# Connector_Schematic.net
KiCad netlist of a schematic drawn in Altium Designer
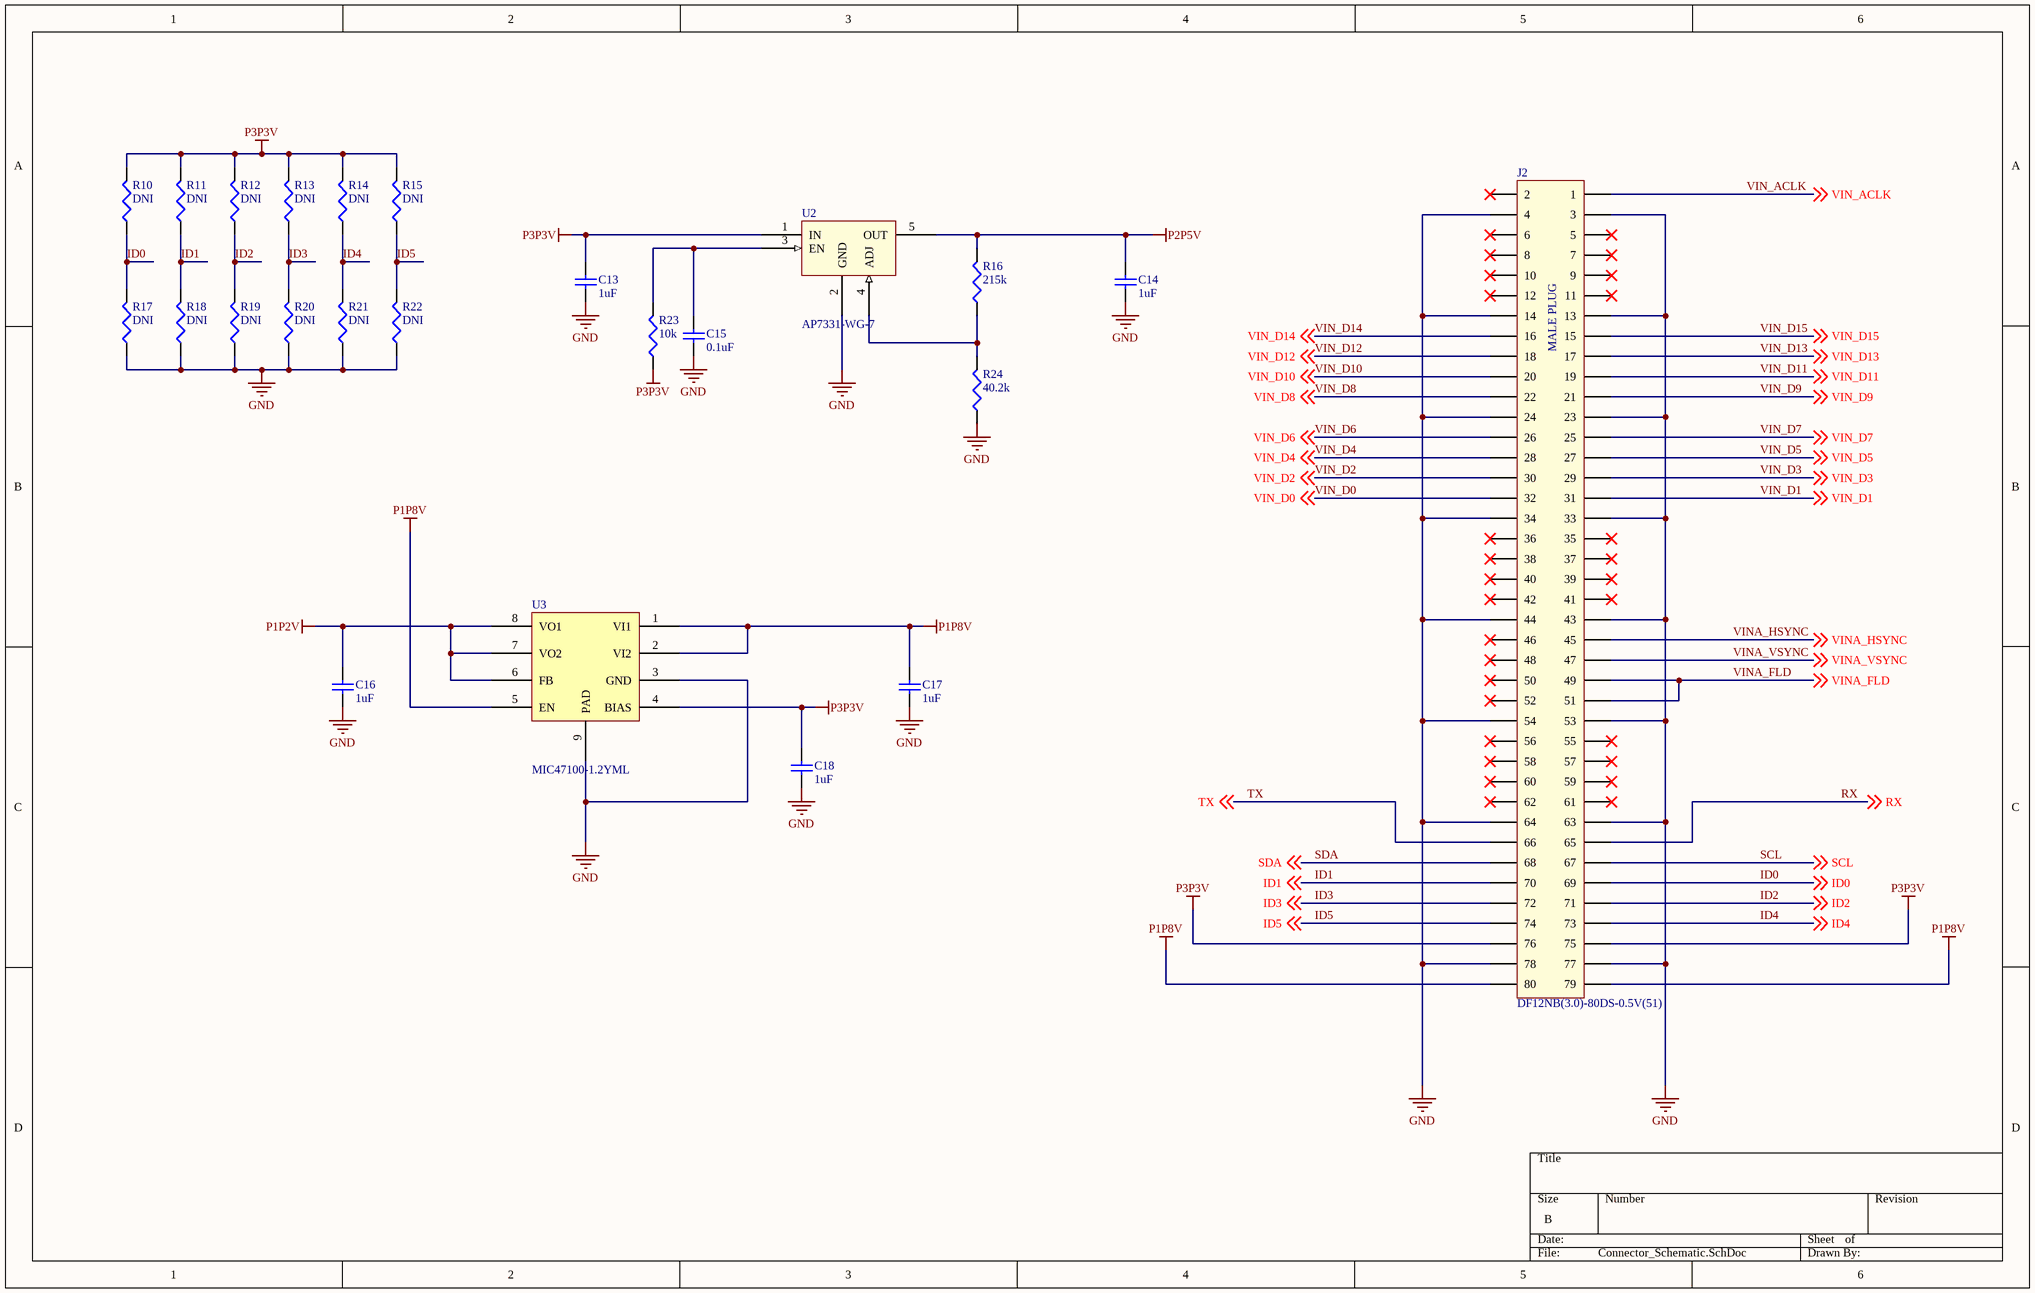
[diagram p0: Connector_Schematic.SchDoc]

(export (version "E")
  (design (tool "Eeschema 10.0.6"))
  (components
    (comp (ref "C13")
      (value "1uF")
      (footprint "INDC1005X45")
      (description "CAP CER 1UF 25V X5R 0402")
      (fields (field (name "MFGPARTNO") "EMK105BJ105KV-F") (field (name "MFG") "Taiyo Yuden"))
      (libsource (lib "SLA3000-FPGA[4086]") (part "CMP-00695-A.2"))
    )
    (comp (ref "C14")
      (value "1uF")
      (footprint "INDC1005X45")
      (description "CAP CER 1UF 25V X5R 0402")
      (fields (field (name "MFGPARTNO") "EMK105BJ105KV-F") (field (name "MFG") "Taiyo Yuden"))
      (libsource (lib "SLA3000-FPGA[4086]") (part "CMP-00695-A.2"))
    )
    (comp (ref "C15")
      (value "0.1uF")
      (footprint "INDC1005X45")
      (description "CAP CER 0.1UF 25V X7R 0402")
      (fields (field (name "SLA PART NO") "SL00150") (field (name "MFG") "TDK"))
      (libsource (lib "SLA3000-FPGA[4086]") (part "CMP-00496-A.6"))
    )
    (comp (ref "C16")
      (value "1uF")
      (footprint "INDC1005X45")
      (description "CAP CER 1UF 25V X5R 0402")
      (fields (field (name "MFGPARTNO") "EMK105BJ105KV-F") (field (name "MFG") "Taiyo Yuden"))
      (libsource (lib "SLA3000-FPGA[4086]") (part "CMP-00695-A.2"))
    )
    (comp (ref "C17")
      (value "1uF")
      (footprint "INDC1005X45")
      (description "CAP CER 1UF 25V X5R 0402")
      (fields (field (name "MFGPARTNO") "EMK105BJ105KV-F") (field (name "MFG") "Taiyo Yuden"))
      (libsource (lib "SLA3000-FPGA[4086]") (part "CMP-00695-A.2"))
    )
    (comp (ref "C18")
      (value "1uF")
      (footprint "INDC1005X45")
      (description "CAP CER 1UF 25V X5R 0402")
      (fields (field (name "MFGPARTNO") "EMK105BJ105KV-F") (field (name "MFG") "Taiyo Yuden"))
      (libsource (lib "SLA3000-FPGA[4086]") (part "CMP-00695-A.2"))
    )
    (comp (ref "J2")
      (value "DF12NB(3.0)-80DS-0.5V(51)")
      (footprint "DF12NB(3.0)-80DS-0.5V(51)")
      (description "DF12NB(3.0)-80DS-0.5V(51) HIROSE CONN HEADER 80POS 3MM SMD 0.5MM")
      (fields (field (name "MFG") "Hirose"))
      (libsource (lib "SLA3000-FPGA[4086]") (part "CMP-00854-A.1"))
    )
    (comp (ref "R10")
      (value "DNI")
      (footprint "RES_ERJU02F1241X")
      (description "Do Not Populate 0402 Res")
      (libsource (lib "SLA3000-FPGA[4086]") (part "CMP-00432-A.10"))
    )
    (comp (ref "R11")
      (value "DNI")
      (footprint "RES_ERJU02F1241X")
      (description "Do Not Populate 0402 Res")
      (libsource (lib "SLA3000-FPGA[4086]") (part "CMP-00432-A.10"))
    )
    (comp (ref "R12")
      (value "DNI")
      (footprint "RES_ERJU02F1241X")
      (description "Do Not Populate 0402 Res")
      (libsource (lib "SLA3000-FPGA[4086]") (part "CMP-00432-A.10"))
    )
    (comp (ref "R13")
      (value "DNI")
      (footprint "RES_ERJU02F1241X")
      (description "Do Not Populate 0402 Res")
      (libsource (lib "SLA3000-FPGA[4086]") (part "CMP-00432-A.10"))
    )
    (comp (ref "R14")
      (value "DNI")
      (footprint "RES_ERJU02F1241X")
      (description "Do Not Populate 0402 Res")
      (libsource (lib "SLA3000-FPGA[4086]") (part "CMP-00432-A.10"))
    )
    (comp (ref "R15")
      (value "DNI")
      (footprint "RES_ERJU02F1241X")
      (description "Do Not Populate 0402 Res")
      (libsource (lib "SLA3000-FPGA[4086]") (part "CMP-00432-A.10"))
    )
    (comp (ref "R16")
      (value "215k")
      (footprint "RES_ERJU02F1241X")
      (description "RES SMD 215K OHM 1% 1/16W 0402")
      (fields (field (name "MFGPARTNO") "RC0402FR-07215KL") (field (name "MFG") "Yageo"))
      (libsource (lib "SLA3000-FPGA[4086]") (part "CMP-00638-A.1"))
    )
    (comp (ref "R17")
      (value "DNI")
      (footprint "RES_ERJU02F1241X")
      (description "Do Not Populate 0402 Res")
      (libsource (lib "SLA3000-FPGA[4086]") (part "CMP-00432-A.10"))
    )
    (comp (ref "R18")
      (value "DNI")
      (footprint "RES_ERJU02F1241X")
      (description "Do Not Populate 0402 Res")
      (libsource (lib "SLA3000-FPGA[4086]") (part "CMP-00432-A.10"))
    )
    (comp (ref "R19")
      (value "DNI")
      (footprint "RES_ERJU02F1241X")
      (description "Do Not Populate 0402 Res")
      (libsource (lib "SLA3000-FPGA[4086]") (part "CMP-00432-A.10"))
    )
    (comp (ref "R20")
      (value "DNI")
      (footprint "RES_ERJU02F1241X")
      (description "Do Not Populate 0402 Res")
      (libsource (lib "SLA3000-FPGA[4086]") (part "CMP-00432-A.10"))
    )
    (comp (ref "R21")
      (value "DNI")
      (footprint "RES_ERJU02F1241X")
      (description "Do Not Populate 0402 Res")
      (libsource (lib "SLA3000-FPGA[4086]") (part "CMP-00432-A.10"))
    )
    (comp (ref "R22")
      (value "DNI")
      (footprint "RES_ERJU02F1241X")
      (description "Do Not Populate 0402 Res")
      (libsource (lib "SLA3000-FPGA[4086]") (part "CMP-00432-A.10"))
    )
    (comp (ref "R23")
      (value "10k")
      (footprint "RES_ERJU02F1241X")
      (description "RES SMD 10K OHM 1% 1/10W 0402")
      (fields (field (name "SLA PART NO") "SL00225") (field (name "MFG") "Panasonic"))
      (libsource (lib "SLA3000-FPGA[4086]") (part "CMP-00396-A.9"))
    )
    (comp (ref "R24")
      (value "40.2k")
      (footprint "RES_ERJU02F1241X")
      (description "RES 40.2K OHM 1/10W 1% 0402 SMD")
      (fields (field (name "SLA PART NO") "SL00235") (field (name "MFGPARTNO") "ERJ-2RKF4022X"))
      (libsource (lib "SLA3000-FPGA[4086]") (part "CMP-00410-A.9"))
    )
    (comp (ref "U2")
      (value "AP7331-WG-7")
      (footprint "SOT95P285X140-5N")
      (description "Adj 0.8-5V Out, 2-6V In, 300mA, AP7331-WG-7 LDO SOT23-5")
      (fields (field (name "SLA PART NO") "SL00740") (field (name "MFG") "Diodes Inc."))
      (libsource (lib "SLA3000-FPGA[4086]") (part "CMP-00547-A.3"))
    )
    (comp (ref "U3")
      (value "MIC47100-1.2YML")
      (footprint "SON50P250X250X75-9N")
      (description "1.2V, 1A, MIC47100-1.2TML IC REG LDO 8MLF")
      (fields (field (name "MFG") "Micrel") (field (name "SLA PART NO") "SL00247"))
      (libsource (lib "SLA3000-FPGA[4086]") (part "CMP-00239-A.3"))
    )
  )
  (nets
    (net (code "1") (name "GND") (class "Default")
      (node (ref "C13") (pin "1") (pinfunction "1_1") (pintype "passive"))
      (node (ref "C14") (pin "1") (pinfunction "1_1") (pintype "passive"))
      (node (ref "C15") (pin "1") (pinfunction "1_1") (pintype "passive"))
      (node (ref "C16") (pin "1") (pinfunction "1_1") (pintype "passive"))
      (node (ref "C17") (pin "1") (pinfunction "1_1") (pintype "passive"))
      (node (ref "C18") (pin "1") (pinfunction "1_1") (pintype "passive"))
      (node (ref "J2") (pin "13") (pinfunction "13_13") (pintype "passive"))
      (node (ref "J2") (pin "14") (pinfunction "14_14") (pintype "passive"))
      (node (ref "J2") (pin "23") (pinfunction "23_23") (pintype "passive"))
      (node (ref "J2") (pin "24") (pinfunction "24_24") (pintype "passive"))
      (node (ref "J2") (pin "3") (pinfunction "3_3") (pintype "passive"))
      (node (ref "J2") (pin "33") (pinfunction "33_33") (pintype "passive"))
      (node (ref "J2") (pin "34") (pinfunction "34_34") (pintype "passive"))
      (node (ref "J2") (pin "4") (pinfunction "4_4") (pintype "passive"))
      (node (ref "J2") (pin "43") (pinfunction "43_43") (pintype "passive"))
      (node (ref "J2") (pin "44") (pinfunction "44_44") (pintype "passive"))
      (node (ref "J2") (pin "53") (pinfunction "53_53") (pintype "passive"))
      (node (ref "J2") (pin "54") (pinfunction "54_54") (pintype "passive"))
      (node (ref "J2") (pin "63") (pinfunction "63_63") (pintype "passive"))
      (node (ref "J2") (pin "64") (pinfunction "64_64") (pintype "passive"))
      (node (ref "J2") (pin "77") (pinfunction "77_77") (pintype "passive"))
      (node (ref "J2") (pin "78") (pinfunction "78_78") (pintype "passive"))
      (node (ref "R17") (pin "1") (pinfunction "1_1") (pintype "passive"))
      (node (ref "R18") (pin "1") (pinfunction "1_1") (pintype "passive"))
      (node (ref "R19") (pin "1") (pinfunction "1_1") (pintype "passive"))
      (node (ref "R20") (pin "1") (pinfunction "1_1") (pintype "passive"))
      (node (ref "R21") (pin "1") (pinfunction "1_1") (pintype "passive"))
      (node (ref "R22") (pin "1") (pinfunction "1_1") (pintype "passive"))
      (node (ref "R24") (pin "1") (pinfunction "1_1") (pintype "passive"))
      (node (ref "U2") (pin "2") (pinfunction "GND_2") (pintype "power_in"))
      (node (ref "U3") (pin "3") (pinfunction "GND_3") (pintype "passive"))
      (node (ref "U3") (pin "9") (pinfunction "PAD_9") (pintype "passive"))
    )
    (net (code "2") (name "ID0") (class "Default")
      (node (ref "J2") (pin "69") (pinfunction "69_69") (pintype "passive"))
      (node (ref "R10") (pin "1") (pinfunction "1_1") (pintype "passive"))
      (node (ref "R17") (pin "2") (pinfunction "2_2") (pintype "passive"))
    )
    (net (code "3") (name "ID1") (class "Default")
      (node (ref "J2") (pin "70") (pinfunction "70_70") (pintype "passive"))
      (node (ref "R11") (pin "1") (pinfunction "1_1") (pintype "passive"))
      (node (ref "R18") (pin "2") (pinfunction "2_2") (pintype "passive"))
    )
    (net (code "4") (name "ID2") (class "Default")
      (node (ref "J2") (pin "71") (pinfunction "71_71") (pintype "passive"))
      (node (ref "R12") (pin "1") (pinfunction "1_1") (pintype "passive"))
      (node (ref "R19") (pin "2") (pinfunction "2_2") (pintype "passive"))
    )
    (net (code "5") (name "ID3") (class "Default")
      (node (ref "J2") (pin "72") (pinfunction "72_72") (pintype "passive"))
      (node (ref "R13") (pin "1") (pinfunction "1_1") (pintype "passive"))
      (node (ref "R20") (pin "2") (pinfunction "2_2") (pintype "passive"))
    )
    (net (code "6") (name "ID4") (class "Default")
      (node (ref "J2") (pin "73") (pinfunction "73_73") (pintype "passive"))
      (node (ref "R14") (pin "1") (pinfunction "1_1") (pintype "passive"))
      (node (ref "R21") (pin "2") (pinfunction "2_2") (pintype "passive"))
    )
    (net (code "7") (name "ID5") (class "Default")
      (node (ref "J2") (pin "74") (pinfunction "74_74") (pintype "passive"))
      (node (ref "R15") (pin "1") (pinfunction "1_1") (pintype "passive"))
      (node (ref "R22") (pin "2") (pinfunction "2_2") (pintype "passive"))
    )
    (net (code "8") (name "Net-(U2-ADJ)") (class "Default")
      (node (ref "R16") (pin "1") (pinfunction "1_1") (pintype "passive"))
      (node (ref "R24") (pin "2") (pinfunction "2_2") (pintype "passive"))
      (node (ref "U2") (pin "4") (pinfunction "ADJ_4") (pintype "input"))
    )
    (net (code "9") (name "Net-(U2-EN)") (class "Default")
      (node (ref "C15") (pin "2") (pinfunction "2_2") (pintype "passive"))
      (node (ref "R23") (pin "2") (pinfunction "2_2") (pintype "passive"))
      (node (ref "U2") (pin "3") (pinfunction "EN_3") (pintype "input"))
    )
    (net (code "10") (name "P1P2V") (class "Default")
      (node (ref "C16") (pin "2") (pinfunction "2_2") (pintype "passive"))
      (node (ref "U3") (pin "6") (pinfunction "FB_6") (pintype "passive"))
      (node (ref "U3") (pin "7") (pinfunction "VO2_7") (pintype "passive"))
      (node (ref "U3") (pin "8") (pinfunction "VO1_8") (pintype "passive"))
    )
    (net (code "11") (name "P1P8V") (class "Default")
      (node (ref "C17") (pin "2") (pinfunction "2_2") (pintype "passive"))
      (node (ref "J2") (pin "79") (pinfunction "79_79") (pintype "passive"))
      (node (ref "J2") (pin "80") (pinfunction "80_80") (pintype "passive"))
      (node (ref "U3") (pin "1") (pinfunction "VI1_1") (pintype "passive"))
      (node (ref "U3") (pin "2") (pinfunction "VI2_2") (pintype "passive"))
      (node (ref "U3") (pin "5") (pinfunction "EN_5") (pintype "passive"))
    )
    (net (code "12") (name "P2P5V") (class "Default")
      (node (ref "C14") (pin "2") (pinfunction "2_2") (pintype "passive"))
      (node (ref "R16") (pin "2") (pinfunction "2_2") (pintype "passive"))
      (node (ref "U2") (pin "5") (pinfunction "OUT_5") (pintype "power_in"))
    )
    (net (code "13") (name "P3P3V") (class "Default")
      (node (ref "C13") (pin "2") (pinfunction "2_2") (pintype "passive"))
      (node (ref "C18") (pin "2") (pinfunction "2_2") (pintype "passive"))
      (node (ref "J2") (pin "75") (pinfunction "75_75") (pintype "passive"))
      (node (ref "J2") (pin "76") (pinfunction "76_76") (pintype "passive"))
      (node (ref "R10") (pin "2") (pinfunction "2_2") (pintype "passive"))
      (node (ref "R11") (pin "2") (pinfunction "2_2") (pintype "passive"))
      (node (ref "R12") (pin "2") (pinfunction "2_2") (pintype "passive"))
      (node (ref "R13") (pin "2") (pinfunction "2_2") (pintype "passive"))
      (node (ref "R14") (pin "2") (pinfunction "2_2") (pintype "passive"))
      (node (ref "R15") (pin "2") (pinfunction "2_2") (pintype "passive"))
      (node (ref "R23") (pin "1") (pinfunction "1_1") (pintype "passive"))
      (node (ref "U2") (pin "1") (pinfunction "IN_1") (pintype "power_in"))
      (node (ref "U3") (pin "4") (pinfunction "BIAS_4") (pintype "passive"))
    )
    (net (code "14") (name "RX") (class "Default")
      (node (ref "J2") (pin "65") (pinfunction "65_65") (pintype "passive"))
    )
    (net (code "15") (name "SCL") (class "Default")
      (node (ref "J2") (pin "67") (pinfunction "67_67") (pintype "passive"))
    )
    (net (code "16") (name "SDA") (class "Default")
      (node (ref "J2") (pin "68") (pinfunction "68_68") (pintype "passive"))
    )
    (net (code "17") (name "TX") (class "Default")
      (node (ref "J2") (pin "66") (pinfunction "66_66") (pintype "passive"))
    )
    (net (code "18") (name "VINA_FLD") (class "Default")
      (node (ref "J2") (pin "49") (pinfunction "49_49") (pintype "passive"))
      (node (ref "J2") (pin "51") (pinfunction "51_51") (pintype "passive"))
    )
    (net (code "19") (name "VINA_HSYNC") (class "Default")
      (node (ref "J2") (pin "45") (pinfunction "45_45") (pintype "passive"))
    )
    (net (code "20") (name "VINA_VSYNC") (class "Default")
      (node (ref "J2") (pin "47") (pinfunction "47_47") (pintype "passive"))
    )
    (net (code "21") (name "VIN_ACLK") (class "Default")
      (node (ref "J2") (pin "1") (pinfunction "1_1") (pintype "passive"))
    )
    (net (code "22") (name "VIN_D0") (class "Default")
      (node (ref "J2") (pin "32") (pinfunction "32_32") (pintype "passive"))
    )
    (net (code "23") (name "VIN_D1") (class "Default")
      (node (ref "J2") (pin "31") (pinfunction "31_31") (pintype "passive"))
    )
    (net (code "24") (name "VIN_D2") (class "Default")
      (node (ref "J2") (pin "30") (pinfunction "30_30") (pintype "passive"))
    )
    (net (code "25") (name "VIN_D3") (class "Default")
      (node (ref "J2") (pin "29") (pinfunction "29_29") (pintype "passive"))
    )
    (net (code "26") (name "VIN_D4") (class "Default")
      (node (ref "J2") (pin "28") (pinfunction "28_28") (pintype "passive"))
    )
    (net (code "27") (name "VIN_D5") (class "Default")
      (node (ref "J2") (pin "27") (pinfunction "27_27") (pintype "passive"))
    )
    (net (code "28") (name "VIN_D6") (class "Default")
      (node (ref "J2") (pin "26") (pinfunction "26_26") (pintype "passive"))
    )
    (net (code "29") (name "VIN_D7") (class "Default")
      (node (ref "J2") (pin "25") (pinfunction "25_25") (pintype "passive"))
    )
    (net (code "30") (name "VIN_D8") (class "Default")
      (node (ref "J2") (pin "22") (pinfunction "22_22") (pintype "passive"))
    )
    (net (code "31") (name "VIN_D9") (class "Default")
      (node (ref "J2") (pin "21") (pinfunction "21_21") (pintype "passive"))
    )
    (net (code "32") (name "VIN_D10") (class "Default")
      (node (ref "J2") (pin "20") (pinfunction "20_20") (pintype "passive"))
    )
    (net (code "33") (name "VIN_D11") (class "Default")
      (node (ref "J2") (pin "19") (pinfunction "19_19") (pintype "passive"))
    )
    (net (code "34") (name "VIN_D12") (class "Default")
      (node (ref "J2") (pin "18") (pinfunction "18_18") (pintype "passive"))
    )
    (net (code "35") (name "VIN_D13") (class "Default")
      (node (ref "J2") (pin "17") (pinfunction "17_17") (pintype "passive"))
    )
    (net (code "36") (name "VIN_D14") (class "Default")
      (node (ref "J2") (pin "16") (pinfunction "16_16") (pintype "passive"))
    )
    (net (code "37") (name "VIN_D15") (class "Default")
      (node (ref "J2") (pin "15") (pinfunction "15_15") (pintype "passive"))
    )
    (net (code "38") (name "unconnected-(J2-Pad2)") (class "Default")
      (node (ref "J2") (pin "2") (pinfunction "2_2") (pintype "passive+no_connect"))
    )
    (net (code "39") (name "unconnected-(J2-Pad5)") (class "Default")
      (node (ref "J2") (pin "5") (pinfunction "5_5") (pintype "passive+no_connect"))
    )
    (net (code "40") (name "unconnected-(J2-Pad6)") (class "Default")
      (node (ref "J2") (pin "6") (pinfunction "6_6") (pintype "passive+no_connect"))
    )
    (net (code "41") (name "unconnected-(J2-Pad7)") (class "Default")
      (node (ref "J2") (pin "7") (pinfunction "7_7") (pintype "passive+no_connect"))
    )
    (net (code "42") (name "unconnected-(J2-Pad8)") (class "Default")
      (node (ref "J2") (pin "8") (pinfunction "8_8") (pintype "passive+no_connect"))
    )
    (net (code "43") (name "unconnected-(J2-Pad9)") (class "Default")
      (node (ref "J2") (pin "9") (pinfunction "9_9") (pintype "passive+no_connect"))
    )
    (net (code "44") (name "unconnected-(J2-Pad10)") (class "Default")
      (node (ref "J2") (pin "10") (pinfunction "10_10") (pintype "passive+no_connect"))
    )
    (net (code "45") (name "unconnected-(J2-Pad11)") (class "Default")
      (node (ref "J2") (pin "11") (pinfunction "11_11") (pintype "passive+no_connect"))
    )
    (net (code "46") (name "unconnected-(J2-Pad12)") (class "Default")
      (node (ref "J2") (pin "12") (pinfunction "12_12") (pintype "passive+no_connect"))
    )
    (net (code "47") (name "unconnected-(J2-Pad35)") (class "Default")
      (node (ref "J2") (pin "35") (pinfunction "35_35") (pintype "passive+no_connect"))
    )
    (net (code "48") (name "unconnected-(J2-Pad36)") (class "Default")
      (node (ref "J2") (pin "36") (pinfunction "36_36") (pintype "passive+no_connect"))
    )
    (net (code "49") (name "unconnected-(J2-Pad37)") (class "Default")
      (node (ref "J2") (pin "37") (pinfunction "37_37") (pintype "passive+no_connect"))
    )
    (net (code "50") (name "unconnected-(J2-Pad38)") (class "Default")
      (node (ref "J2") (pin "38") (pinfunction "38_38") (pintype "passive+no_connect"))
    )
    (net (code "51") (name "unconnected-(J2-Pad39)") (class "Default")
      (node (ref "J2") (pin "39") (pinfunction "39_39") (pintype "passive+no_connect"))
    )
    (net (code "52") (name "unconnected-(J2-Pad40)") (class "Default")
      (node (ref "J2") (pin "40") (pinfunction "40_40") (pintype "passive+no_connect"))
    )
    (net (code "53") (name "unconnected-(J2-Pad41)") (class "Default")
      (node (ref "J2") (pin "41") (pinfunction "41_41") (pintype "passive+no_connect"))
    )
    (net (code "54") (name "unconnected-(J2-Pad42)") (class "Default")
      (node (ref "J2") (pin "42") (pinfunction "42_42") (pintype "passive+no_connect"))
    )
    (net (code "55") (name "unconnected-(J2-Pad46)") (class "Default")
      (node (ref "J2") (pin "46") (pinfunction "46_46") (pintype "passive+no_connect"))
    )
    (net (code "56") (name "unconnected-(J2-Pad48)") (class "Default")
      (node (ref "J2") (pin "48") (pinfunction "48_48") (pintype "passive+no_connect"))
    )
    (net (code "57") (name "unconnected-(J2-Pad50)") (class "Default")
      (node (ref "J2") (pin "50") (pinfunction "50_50") (pintype "passive+no_connect"))
    )
    (net (code "58") (name "unconnected-(J2-Pad52)") (class "Default")
      (node (ref "J2") (pin "52") (pinfunction "52_52") (pintype "passive+no_connect"))
    )
    (net (code "59") (name "unconnected-(J2-Pad55)") (class "Default")
      (node (ref "J2") (pin "55") (pinfunction "55_55") (pintype "passive+no_connect"))
    )
    (net (code "60") (name "unconnected-(J2-Pad56)") (class "Default")
      (node (ref "J2") (pin "56") (pinfunction "56_56") (pintype "passive+no_connect"))
    )
    (net (code "61") (name "unconnected-(J2-Pad57)") (class "Default")
      (node (ref "J2") (pin "57") (pinfunction "57_57") (pintype "passive+no_connect"))
    )
    (net (code "62") (name "unconnected-(J2-Pad58)") (class "Default")
      (node (ref "J2") (pin "58") (pinfunction "58_58") (pintype "passive+no_connect"))
    )
    (net (code "63") (name "unconnected-(J2-Pad59)") (class "Default")
      (node (ref "J2") (pin "59") (pinfunction "59_59") (pintype "passive+no_connect"))
    )
    (net (code "64") (name "unconnected-(J2-Pad60)") (class "Default")
      (node (ref "J2") (pin "60") (pinfunction "60_60") (pintype "passive+no_connect"))
    )
    (net (code "65") (name "unconnected-(J2-Pad61)") (class "Default")
      (node (ref "J2") (pin "61") (pinfunction "61_61") (pintype "passive+no_connect"))
    )
    (net (code "66") (name "unconnected-(J2-Pad62)") (class "Default")
      (node (ref "J2") (pin "62") (pinfunction "62_62") (pintype "passive+no_connect"))
    )
  )
)
